# ETH-PHY.net
KiCad netlist of a schematic drawn in Altium Designer
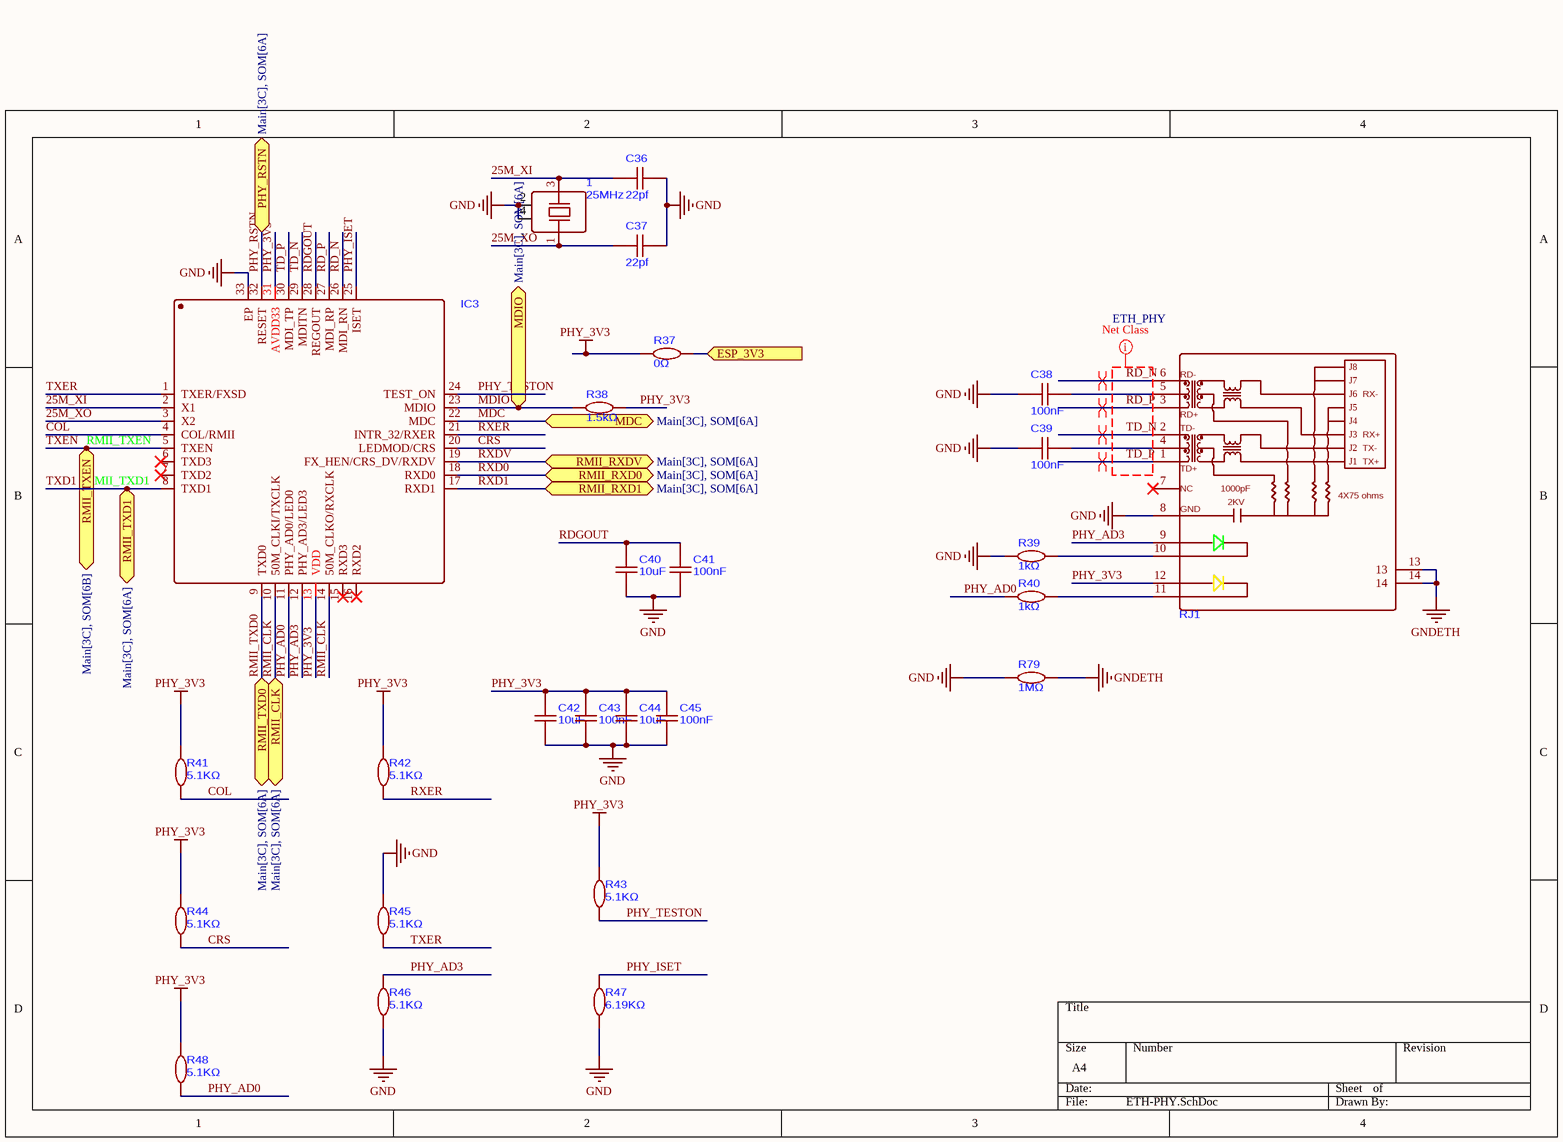
[diagram p0: ETH-PHY.SchDoc]

(export (version "E")
  (design (tool "Eeschema 10.0.6"))
  (components
    (comp (ref "1")
      (value "25MHz")
      (footprint "CRYSTAL-SMD_4P-L3.2-W2.5-BL")
      (libsource (lib "Schlib2") (part "X322525MOB4SI"))
    )
    (comp (ref "C36")
      (value "22pf")
      (footprint "C0603")
      (description "50V 22pF C0G ±5% 0603 Ceramic Capacitors RoHS")
      (libsource (lib "Schlib2") (part "CL10C220JB8NNNC"))
    )
    (comp (ref "C37")
      (value "22pf")
      (footprint "C0603")
      (description "50V 22pF C0G ±5% 0603 Ceramic Capacitors RoHS")
      (libsource (lib "Schlib2") (part "CL10C220JB8NNNC"))
    )
    (comp (ref "C38")
      (value "100nF")
      (footprint "C0603")
      (description "50V 100nF X7R ±10% 0603 Ceramic Capacitors ROHS")
      (libsource (lib "Schlib2") (part "CC0603KRX7R9BB104"))
    )
    (comp (ref "C39")
      (value "100nF")
      (footprint "C0603")
      (description "50V 100nF X7R ±10% 0603 Ceramic Capacitors ROHS")
      (libsource (lib "Schlib2") (part "CC0603KRX7R9BB104"))
    )
    (comp (ref "C40")
      (value "10uF")
      (footprint "C0603")
      (description "25V 10uF X5R ±20% 0603 Ceramic Capacitors ROHS")
      (libsource (lib "Schlib2") (part "CL10A106MA8NRNC"))
    )
    (comp (ref "C41")
      (value "100nF")
      (footprint "C0603")
      (description "50V 100nF X7R ±10% 0603 Ceramic Capacitors ROHS")
      (libsource (lib "Schlib2") (part "CC0603KRX7R9BB104"))
    )
    (comp (ref "C42")
      (value "10uF")
      (footprint "C0603")
      (description "25V 10uF X5R ±20% 0603 Ceramic Capacitors ROHS")
      (libsource (lib "Schlib2") (part "CL10A106MA8NRNC"))
    )
    (comp (ref "C43")
      (value "100nF")
      (footprint "C0603")
      (description "50V 100nF X7R ±10% 0603 Ceramic Capacitors ROHS")
      (libsource (lib "Schlib2") (part "CC0603KRX7R9BB104"))
    )
    (comp (ref "C44")
      (value "10uF")
      (footprint "C0603")
      (description "25V 10uF X5R ±20% 0603 Ceramic Capacitors ROHS")
      (libsource (lib "Schlib2") (part "CL10A106MA8NRNC"))
    )
    (comp (ref "C45")
      (value "100nF")
      (footprint "C0603")
      (description "50V 100nF X7R ±10% 0603 Ceramic Capacitors ROHS")
      (libsource (lib "Schlib2") (part "CC0603KRX7R9BB104"))
    )
    (comp (ref "IC3")
      (value "Single Port Fast Ethernet Transceiver")
      (footprint "QFN-32_L4.0-W4.0-P0.40-BL-EP2.7")
      (description "Ethernet Transceiver 3.3V QFN-32-EP(4x4) Drivers, Receivers, Transceivers RoHS")
      (libsource (lib "Schlib2") (part "IP101GRI"))
    )
    (comp (ref "R37")
      (value "0Ω")
      (footprint "R0603")
      (description "100mW 0Ω 75V Thick Film Resistor ±5% 0603 Chip Resistor - Surface Mount RoHS")
      (libsource (lib "Schlib2") (part "RC0603JR-070RL"))
    )
    (comp (ref "R38")
      (value "1.5kΩ")
      (footprint "R0603")
      (description "100mW 1.5kΩ 75V ±100ppm/℃ Thick Film Resistor ±1% 0603 Chip Resistor - Surface Mount RoHS")
      (libsource (lib "Schlib2") (part "RC0603FR-071K5L"))
    )
    (comp (ref "R39")
      (value "1kΩ")
      (footprint "R0603")
      (description "100mW 1kΩ 50V ±100ppm/℃ Thick Film Resistor ±5% 0603 Chip Resistor - Surface Mount ROHS")
      (libsource (lib "Schlib2") (part "RMC 0603 1K J N"))
    )
    (comp (ref "R40")
      (value "1kΩ")
      (footprint "R0603")
      (description "100mW 1kΩ 50V ±100ppm/℃ Thick Film Resistor ±5% 0603 Chip Resistor - Surface Mount ROHS")
      (libsource (lib "Schlib2") (part "RMC 0603 1K J N"))
    )
    (comp (ref "R41")
      (value "5.1KΩ")
      (footprint "R0603")
      (description "100mW 5.1kΩ 75V ±100ppm/℃ Thick Film Resistor ±1% 0603 Chip Resistor - Surface Mount RoHS")
      (libsource (lib "Schlib2") (part "FRC0603F5101TS"))
    )
    (comp (ref "R42")
      (value "5.1KΩ")
      (footprint "R0603")
      (description "100mW 5.1kΩ 75V ±100ppm/℃ Thick Film Resistor ±1% 0603 Chip Resistor - Surface Mount RoHS")
      (libsource (lib "Schlib2") (part "FRC0603F5101TS"))
    )
    (comp (ref "R43")
      (value "5.1KΩ")
      (footprint "R0603")
      (description "100mW 5.1kΩ 75V ±100ppm/℃ Thick Film Resistor ±1% 0603 Chip Resistor - Surface Mount RoHS")
      (libsource (lib "Schlib2") (part "FRC0603F5101TS"))
    )
    (comp (ref "R44")
      (value "5.1KΩ")
      (footprint "R0603")
      (description "100mW 5.1kΩ 75V ±100ppm/℃ Thick Film Resistor ±1% 0603 Chip Resistor - Surface Mount RoHS")
      (libsource (lib "Schlib2") (part "FRC0603F5101TS"))
    )
    (comp (ref "R45")
      (value "5.1KΩ")
      (footprint "R0603")
      (description "100mW 5.1kΩ 75V ±100ppm/℃ Thick Film Resistor ±1% 0603 Chip Resistor - Surface Mount RoHS")
      (libsource (lib "Schlib2") (part "FRC0603F5101TS"))
    )
    (comp (ref "R46")
      (value "5.1KΩ")
      (footprint "R0603")
      (description "100mW 5.1kΩ 75V ±100ppm/℃ Thick Film Resistor ±1% 0603 Chip Resistor - Surface Mount RoHS")
      (libsource (lib "Schlib2") (part "FRC0603F5101TS"))
    )
    (comp (ref "R47")
      (value "6.19KΩ")
      (footprint "R0603")
      (description "6.19kΩ 100mW 75V ±100ppm/℃ Thick Film Resistor ±1% 0603 Chip Resistor - Surface Mount RoHS")
      (libsource (lib "Schlib2") (part "AC0603FR-076K19L"))
    )
    (comp (ref "R48")
      (value "5.1KΩ")
      (footprint "R0603")
      (description "100mW 5.1kΩ 75V ±100ppm/℃ Thick Film Resistor ±1% 0603 Chip Resistor - Surface Mount RoHS")
      (libsource (lib "Schlib2") (part "FRC0603F5101TS"))
    )
    (comp (ref "R79")
      (value "1MΩ")
      (footprint "R2010")
      (description "100mW 1MΩ 75V Thick Film Resistor ±100ppm/℃ ±1% 0603 Chip Resistor - Surface Mount RoHS")
      (libsource (lib "Schlib2") (part "RC0603FR-071ML"))
    )
    (comp (ref "RJ1")
      (value "CONN MOD JACK RJ45 TH")
      (footprint "RJ45-TH_HR913550A")
      (description "1 With LED Through Hole Modular/Ethernet Connector Jacks With Magnetics RoHS")
      (libsource (lib "Schlib2") (part "HR913550A"))
    )
  )
  (nets
    (net (code "1") (name "/25M_XI") (class "Default")
      (node (ref "1") (pin "3") (pinfunction "OSC2_3") (pintype "passive"))
      (node (ref "C36") (pin "1") (pinfunction "1_1") (pintype "passive"))
      (node (ref "IC3") (pin "2") (pinfunction "X1_2") (pintype "passive"))
    )
    (net (code "2") (name "/25M_XO") (class "Default")
      (node (ref "1") (pin "1") (pinfunction "OSC1_1") (pintype "passive"))
      (node (ref "C37") (pin "1") (pinfunction "1_1") (pintype "passive"))
      (node (ref "IC3") (pin "3") (pinfunction "X2_3") (pintype "passive"))
    )
    (net (code "3") (name "/COL") (class "Default")
      (node (ref "IC3") (pin "4") (pinfunction "COL/RMII_4") (pintype "passive"))
      (node (ref "R41") (pin "1") (pinfunction "1_1") (pintype "passive"))
    )
    (net (code "4") (name "/CRS") (class "Default")
      (node (ref "IC3") (pin "20") (pinfunction "LEDMOD/CRS_20") (pintype "passive"))
      (node (ref "R44") (pin "1") (pinfunction "1_1") (pintype "passive"))
    )
    (net (code "5") (name "/ESP_3V3") (class "Default")
      (node (ref "R37") (pin "2") (pinfunction "2_2") (pintype "passive"))
    )
    (net (code "6") (name "/MDC") (class "Default")
      (node (ref "IC3") (pin "22") (pinfunction "MDC_22") (pintype "passive"))
    )
    (net (code "7") (name "/MDIO") (class "Default")
      (node (ref "IC3") (pin "23") (pinfunction "MDIO_23") (pintype "passive"))
      (node (ref "R38") (pin "1") (pinfunction "1_1") (pintype "passive"))
    )
    (net (code "8") (name "/PHY_AD0") (class "Default")
      (node (ref "IC3") (pin "11") (pinfunction "PHY_AD0/LED0_11") (pintype "passive"))
      (node (ref "R40") (pin "1") (pinfunction "1_1") (pintype "passive"))
      (node (ref "R48") (pin "1") (pinfunction "1_1") (pintype "passive"))
    )
    (net (code "9") (name "/PHY_AD3") (class "Default")
      (node (ref "IC3") (pin "12") (pinfunction "PHY_AD3/LED3_12") (pintype "passive"))
      (node (ref "R46") (pin "1") (pinfunction "1_1") (pintype "passive"))
      (node (ref "RJ1") (pin "9") (pintype "passive"))
    )
    (net (code "10") (name "/PHY_ISET") (class "Default")
      (node (ref "IC3") (pin "25") (pinfunction "ISET_25") (pintype "passive"))
      (node (ref "R47") (pin "2") (pinfunction "2_2") (pintype "passive"))
    )
    (net (code "11") (name "/PHY_RSTN") (class "Default")
      (node (ref "IC3") (pin "32") (pinfunction "RESET_32") (pintype "passive"))
    )
    (net (code "12") (name "/PHY_TESTON") (class "Default")
      (node (ref "IC3") (pin "24") (pinfunction "TEST_ON_24") (pintype "passive"))
      (node (ref "R43") (pin "1") (pinfunction "1_1") (pintype "passive"))
    )
    (net (code "13") (name "/RDGOUT") (class "Default")
      (node (ref "C40") (pin "2") (pinfunction "2_2") (pintype "passive"))
      (node (ref "C41") (pin "2") (pinfunction "2_2") (pintype "passive"))
      (node (ref "IC3") (pin "28") (pinfunction "REGOUT_28") (pintype "passive"))
    )
    (net (code "14") (name "/RD_N") (class "Default")
      (node (ref "IC3") (pin "26") (pinfunction "MDI_RN_26") (pintype "passive"))
      (node (ref "RJ1") (pin "6") (pintype "passive"))
    )
    (net (code "15") (name "/RD_P") (class "Default")
      (node (ref "IC3") (pin "27") (pinfunction "MDI_RP_27") (pintype "passive"))
      (node (ref "RJ1") (pin "3") (pintype "passive"))
    )
    (net (code "16") (name "/RMII_CLK") (class "Default")
      (node (ref "IC3") (pin "10") (pinfunction "50M_CLKI/TXCLK_10") (pintype "passive"))
      (node (ref "IC3") (pin "14") (pinfunction "50M_CLKO/RXCLK_14") (pintype "passive"))
    )
    (net (code "17") (name "/RMII_TXD0") (class "Default")
      (node (ref "IC3") (pin "9") (pinfunction "TXD0_9") (pintype "passive"))
    )
    (net (code "18") (name "/RMII_TXD1") (class "Default")
      (node (ref "IC3") (pin "8") (pinfunction "TXD1_8") (pintype "passive"))
    )
    (net (code "19") (name "/RMII_TXEN") (class "Default")
      (node (ref "IC3") (pin "5") (pinfunction "TXEN_5") (pintype "passive"))
    )
    (net (code "20") (name "/RXD0") (class "Default")
      (node (ref "IC3") (pin "18") (pinfunction "RXD0_18") (pintype "passive"))
    )
    (net (code "21") (name "/RXD1") (class "Default")
      (node (ref "IC3") (pin "17") (pinfunction "RXD1_17") (pintype "passive"))
    )
    (net (code "22") (name "/RXDV") (class "Default")
      (node (ref "IC3") (pin "19") (pinfunction "FX_HEN/CRS_DV/RXDV_19") (pintype "passive"))
    )
    (net (code "23") (name "/RXER") (class "Default")
      (node (ref "IC3") (pin "21") (pinfunction "INTR_32/RXER_21") (pintype "passive"))
      (node (ref "R42") (pin "1") (pinfunction "1_1") (pintype "passive"))
    )
    (net (code "24") (name "/TD_N") (class "Default")
      (node (ref "IC3") (pin "29") (pinfunction "MDITN_29") (pintype "passive"))
      (node (ref "RJ1") (pin "2") (pintype "passive"))
    )
    (net (code "25") (name "/TD_P") (class "Default")
      (node (ref "IC3") (pin "30") (pinfunction "MDI_TP_30") (pintype "passive"))
      (node (ref "RJ1") (pin "1") (pintype "passive"))
    )
    (net (code "26") (name "/TXER") (class "Default")
      (node (ref "IC3") (pin "1") (pinfunction "TXER/FXSD_1") (pintype "passive"))
      (node (ref "R45") (pin "1") (pinfunction "1_1") (pintype "passive"))
    )
    (net (code "27") (name "GND") (class "Default")
      (node (ref "1") (pin "2") (pinfunction "GND_2") (pintype "passive"))
      (node (ref "1") (pin "4") (pinfunction "GND_4") (pintype "passive"))
      (node (ref "C36") (pin "2") (pinfunction "2_2") (pintype "passive"))
      (node (ref "C37") (pin "2") (pinfunction "2_2") (pintype "passive"))
      (node (ref "C38") (pin "1") (pinfunction "1_1") (pintype "passive"))
      (node (ref "C39") (pin "1") (pinfunction "1_1") (pintype "passive"))
      (node (ref "C40") (pin "1") (pinfunction "1_1") (pintype "passive"))
      (node (ref "C41") (pin "1") (pinfunction "1_1") (pintype "passive"))
      (node (ref "C42") (pin "1") (pinfunction "1_1") (pintype "passive"))
      (node (ref "C43") (pin "1") (pinfunction "1_1") (pintype "passive"))
      (node (ref "C44") (pin "1") (pinfunction "1_1") (pintype "passive"))
      (node (ref "C45") (pin "1") (pinfunction "1_1") (pintype "passive"))
      (node (ref "IC3") (pin "33") (pinfunction "EP_33") (pintype "passive"))
      (node (ref "R39") (pin "1") (pinfunction "1_1") (pintype "passive"))
      (node (ref "R45") (pin "2") (pinfunction "2_2") (pintype "passive"))
      (node (ref "R46") (pin "2") (pinfunction "2_2") (pintype "passive"))
      (node (ref "R47") (pin "1") (pinfunction "1_1") (pintype "passive"))
      (node (ref "R79") (pin "1") (pinfunction "1_1") (pintype "passive"))
      (node (ref "RJ1") (pin "8") (pinfunction "GND_8") (pintype "passive"))
    )
    (net (code "28") (name "GNDETH") (class "Default")
      (node (ref "R79") (pin "2") (pinfunction "2_2") (pintype "passive"))
      (node (ref "RJ1") (pin "13") (pinfunction "13_13") (pintype "passive"))
      (node (ref "RJ1") (pin "14") (pinfunction "14_14") (pintype "passive"))
    )
    (net (code "29") (name "Net-(C38-Pad2)") (class "Default")
      (node (ref "C38") (pin "2") (pinfunction "2_2") (pintype "passive"))
      (node (ref "RJ1") (pin "5") (pintype "passive"))
    )
    (net (code "30") (name "Net-(C39-Pad2)") (class "Default")
      (node (ref "C39") (pin "2") (pinfunction "2_2") (pintype "passive"))
      (node (ref "RJ1") (pin "4") (pintype "passive"))
    )
    (net (code "31") (name "Net-(R39-Pad2)") (class "Default")
      (node (ref "R39") (pin "2") (pinfunction "2_2") (pintype "passive"))
      (node (ref "RJ1") (pin "10") (pintype "passive"))
    )
    (net (code "32") (name "Net-(R40-Pad2)") (class "Default")
      (node (ref "R40") (pin "2") (pinfunction "2_2") (pintype "passive"))
      (node (ref "RJ1") (pin "11") (pintype "passive"))
    )
    (net (code "33") (name "PHY_3V3") (class "Default")
      (node (ref "C42") (pin "2") (pinfunction "2_2") (pintype "passive"))
      (node (ref "C43") (pin "2") (pinfunction "2_2") (pintype "passive"))
      (node (ref "C44") (pin "2") (pinfunction "2_2") (pintype "passive"))
      (node (ref "C45") (pin "2") (pinfunction "2_2") (pintype "passive"))
      (node (ref "IC3") (pin "13") (pinfunction "VDD_13") (pintype "passive"))
      (node (ref "IC3") (pin "31") (pinfunction "AVDD33_31") (pintype "passive"))
      (node (ref "R37") (pin "1") (pinfunction "1_1") (pintype "passive"))
      (node (ref "R38") (pin "2") (pinfunction "2_2") (pintype "passive"))
      (node (ref "R41") (pin "2") (pinfunction "2_2") (pintype "passive"))
      (node (ref "R42") (pin "2") (pinfunction "2_2") (pintype "passive"))
      (node (ref "R43") (pin "2") (pinfunction "2_2") (pintype "passive"))
      (node (ref "R44") (pin "2") (pinfunction "2_2") (pintype "passive"))
      (node (ref "R48") (pin "2") (pinfunction "2_2") (pintype "passive"))
      (node (ref "RJ1") (pin "12") (pintype "passive"))
    )
    (net (code "34") (name "unconnected-(IC3-RXD2-Pad16)") (class "Default")
      (node (ref "IC3") (pin "16") (pinfunction "RXD2_16") (pintype "passive+no_connect"))
    )
    (net (code "35") (name "unconnected-(IC3-RXD3-Pad15)") (class "Default")
      (node (ref "IC3") (pin "15") (pinfunction "RXD3_15") (pintype "passive+no_connect"))
    )
    (net (code "36") (name "unconnected-(IC3-TXD2-Pad7)") (class "Default")
      (node (ref "IC3") (pin "7") (pinfunction "TXD2_7") (pintype "passive+no_connect"))
    )
    (net (code "37") (name "unconnected-(IC3-TXD3-Pad6)") (class "Default")
      (node (ref "IC3") (pin "6") (pinfunction "TXD3_6") (pintype "passive+no_connect"))
    )
    (net (code "38") (name "unconnected-(RJ1-NC-Pad7)") (class "Default")
      (node (ref "RJ1") (pin "7") (pinfunction "NC_7") (pintype "passive+no_connect"))
    )
  )
)
